# tvbgone.net
KiCad netlist of a schematic drawn in EAGLE
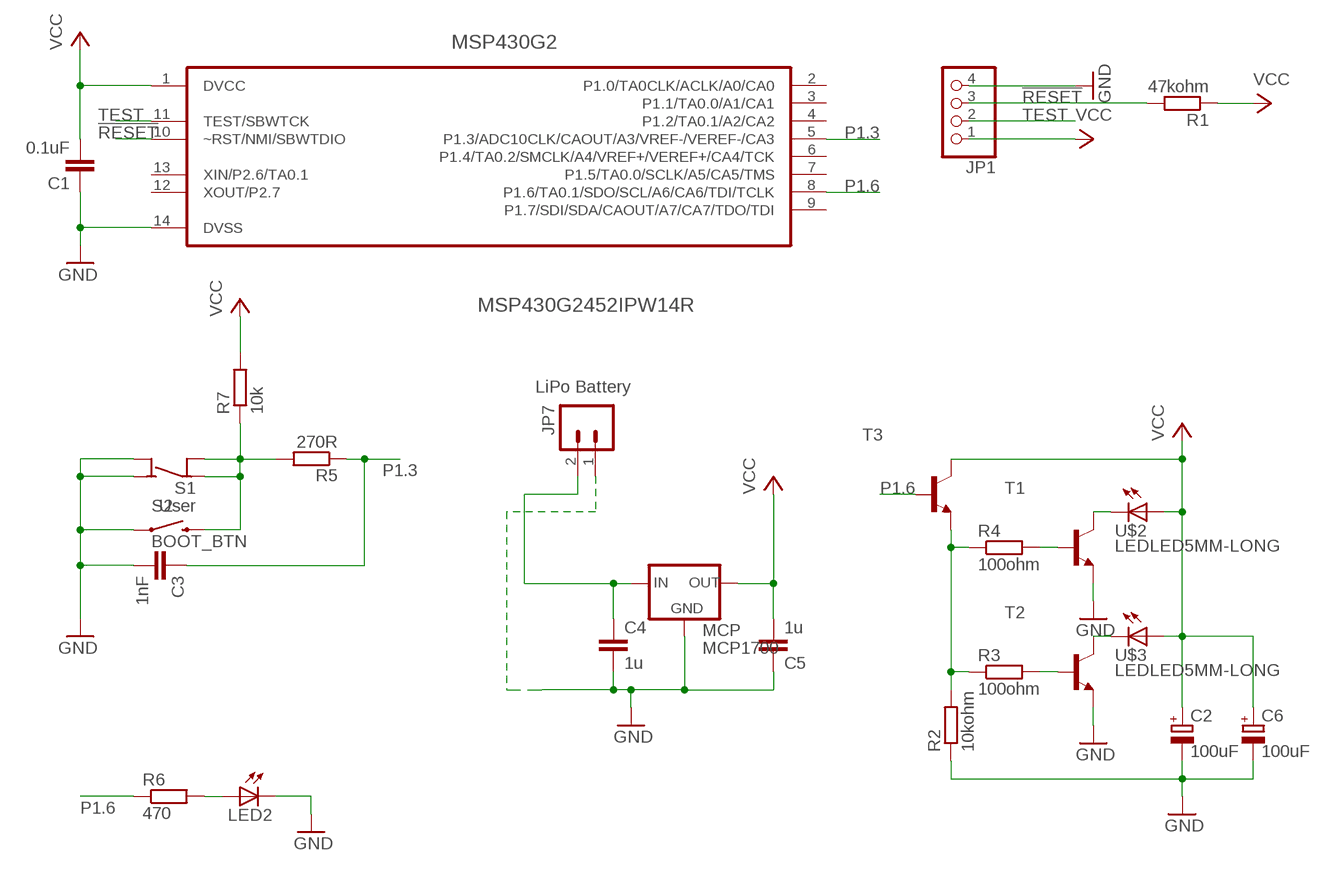
[diagram p0: schematic, sheet 1]

(export (version "E")
  (design (tool "Eeschema 10.0.6"))
  (components
    (comp (ref "C1")
      (value "0.1uF")
      (footprint "eagle-import:C0805")
      (libsource (lib "eagle-import") (part "resistor_C-EUC0805"))
    )
    (comp (ref "C2")
      (value "100uF")
      (footprint "eagle-import:153CLV-0505")
      (libsource (lib "eagle-import") (part "CPOL-EU153CLV-0505"))
    )
    (comp (ref "C3")
      (value "1nF")
      (footprint "eagle-import:C0805")
      (libsource (lib "eagle-import") (part "resistor_C-EUC0805"))
    )
    (comp (ref "C4")
      (value "1u")
      (footprint "eagle-import:C0805")
      (libsource (lib "eagle-import") (part "C-EUC0805"))
    )
    (comp (ref "C5")
      (value "1u")
      (footprint "eagle-import:C0805")
      (libsource (lib "eagle-import") (part "C-EUC0805"))
    )
    (comp (ref "C6")
      (value "100uF")
      (footprint "eagle-import:E3,5-8")
      (libsource (lib "eagle-import") (part "CPOL-EUE3.5-8"))
    )
    (comp (ref "JP1")
      (value "PINHD-1X4")
      (footprint "eagle-import:1X04")
      (libsource (lib "eagle-import") (part "PINHD-1X4"))
    )
    (comp (ref "JP7")
      (value "LiPo Battery")
      (footprint "eagle-import:JST-2-PTH")
      (libsource (lib "eagle-import") (part "M02JST-PTH-2"))
    )
    (comp (ref "LED2")
      (value "0")
      (footprint "eagle-import:CHIPLED_1206")
      (libsource (lib "eagle-import") (part "LEDCHIPLED_1206"))
    )
    (comp (ref "MCP")
      (value "MCP1700")
      (footprint "eagle-import:SOT-23")
      (libsource (lib "eagle-import") (part "MCP1700SOT-23"))
    )
    (comp (ref "MSP430G2")
      (value "MSP430G2452IPW14R")
      (footprint "eagle-import:SOP65P640X120-14N")
      (libsource (lib "eagle-import") (part "MSP430G2452IPW14R"))
    )
    (comp (ref "R1")
      (value "47kohm")
      (footprint "eagle-import:R0805")
      (libsource (lib "eagle-import") (part "R-EU_R0805"))
    )
    (comp (ref "R2")
      (value "10kohm")
      (footprint "eagle-import:R0805")
      (libsource (lib "eagle-import") (part "R-EU_R0805"))
    )
    (comp (ref "R3")
      (value "100ohm")
      (footprint "eagle-import:R0805")
      (libsource (lib "eagle-import") (part "R-EU_R0805"))
    )
    (comp (ref "R4")
      (value "100ohm")
      (footprint "eagle-import:R0805")
      (libsource (lib "eagle-import") (part "R-EU_R0805"))
    )
    (comp (ref "R5")
      (value "270R")
      (footprint "eagle-import:R0805")
      (libsource (lib "eagle-import") (part "R-EU_R0805"))
    )
    (comp (ref "R6")
      (value "470")
      (footprint "eagle-import:R0805")
      (libsource (lib "eagle-import") (part "R-EU_R0805"))
    )
    (comp (ref "R7")
      (value "10k")
      (footprint "eagle-import:R0805")
      (libsource (lib "eagle-import") (part "R-EU_R0805"))
    )
    (comp (ref "S1")
      (value "User")
      (footprint "eagle-import:6MMTACTILE_4PIN")
      (libsource (lib "eagle-import") (part "SPST4"))
    )
    (comp (ref "S2")
      (value "BOOT_BTN")
      (footprint "eagle-import:TACTILE-SWITCH-1101NE")
      (libsource (lib "eagle-import") (part "SWITCH-MOMENTARY-2-SMD-1101NE"))
    )
    (comp (ref "T1")
      (value "MMBT2222ALT1-NPN-SOT23-BEC")
      (footprint "eagle-import:SOT23-BEC")
      (libsource (lib "eagle-import") (part "-NPN-SOT23-BECMMBT2222ALT1"))
    )
    (comp (ref "T2")
      (value "MMBT2222ALT1-NPN-SOT23-BEC")
      (footprint "eagle-import:SOT23-BEC")
      (libsource (lib "eagle-import") (part "-NPN-SOT23-BECMMBT2222ALT1"))
    )
    (comp (ref "T3")
      (value "MMBT2222ALT1-NPN-SOT23-BEC")
      (footprint "eagle-import:SOT23-BEC")
      (libsource (lib "eagle-import") (part "-NPN-SOT23-BECMMBT2222ALT1"))
    )
    (comp (ref "U$2")
      (value "LEDLED5MM-LONG")
      (footprint "eagle-import:LED5MM-LONG")
      (libsource (lib "eagle-import") (part "LEDLED5MM-LONG"))
    )
    (comp (ref "U$3")
      (value "LEDLED5MM-LONG")
      (footprint "eagle-import:LED5MM-LONG")
      (libsource (lib "eagle-import") (part "LEDLED5MM-LONG"))
    )
  )
  (nets
    (net (code "1") (name "/P1.3") (class "Default")
      (node (ref "C3") (pin "1") (pinfunction "1_1") (pintype "passive"))
      (node (ref "MSP430G2") (pin "5") (pinfunction "P1.3/ADC10CLK/CAOUT/A3/VREF-/VEREF-/CA3_5") (pintype "bidirectional"))
      (node (ref "R5") (pin "1") (pinfunction "1_1") (pintype "passive"))
    )
    (net (code "2") (name "/P1.6") (class "Default")
      (node (ref "MSP430G2") (pin "8") (pinfunction "P1.6/TA0.1/SDO/SCL/A6/CA6/TDI/TCLK_8") (pintype "bidirectional"))
      (node (ref "R6") (pin "1") (pinfunction "1_1") (pintype "passive"))
      (node (ref "T3") (pin "B") (pinfunction "B_B") (pintype "passive"))
    )
    (net (code "3") (name "/TEST") (class "Default")
      (node (ref "JP1") (pin "2") (pinfunction "2_2") (pintype "passive"))
      (node (ref "MSP430G2") (pin "11") (pinfunction "TEST/SBWTCK_11") (pintype "input"))
    )
    (net (code "4") (name "/~{RESET}") (class "Default")
      (node (ref "JP1") (pin "3") (pinfunction "3_3") (pintype "passive"))
      (node (ref "MSP430G2") (pin "10") (pinfunction "~{RST/NMI/SBWTDIO}_10") (pintype "input"))
      (node (ref "R1") (pin "2") (pinfunction "2_2") (pintype "passive"))
    )
    (net (code "5") (name "GND") (class "Default")
      (node (ref "C1") (pin "1") (pinfunction "1_1") (pintype "passive"))
      (node (ref "C2") (pin "-") (pinfunction "-_-") (pintype "passive"))
      (node (ref "C3") (pin "2") (pinfunction "2_2") (pintype "passive"))
      (node (ref "C4") (pin "2") (pinfunction "2_2") (pintype "passive"))
      (node (ref "C5") (pin "1") (pinfunction "1_1") (pintype "passive"))
      (node (ref "C6") (pin "-") (pinfunction "-_-") (pintype "passive"))
      (node (ref "JP1") (pin "4") (pinfunction "4_4") (pintype "passive"))
      (node (ref "JP7") (pin "1") (pinfunction "1_1") (pintype "passive"))
      (node (ref "LED2") (pin "C") (pinfunction "C_C") (pintype "passive"))
      (node (ref "MCP") (pin "1") (pinfunction "GND_1") (pintype "input"))
      (node (ref "MSP430G2") (pin "14") (pinfunction "DVSS_14") (pintype "power_in"))
      (node (ref "R2") (pin "1") (pinfunction "1_1") (pintype "passive"))
      (node (ref "S1") (pin "A1") (pinfunction "NO_A1") (pintype "passive"))
      (node (ref "S1") (pin "A2") (pinfunction "NO_A2") (pintype "passive"))
      (node (ref "S2") (pin "1") (pinfunction "1_1") (pintype "passive"))
      (node (ref "T1") (pin "E") (pinfunction "E_E") (pintype "passive"))
      (node (ref "T2") (pin "E") (pinfunction "E_E") (pintype "passive"))
    )
    (net (code "6") (name "Net-(LED2-PadA)") (class "Default")
      (node (ref "LED2") (pin "A") (pinfunction "A_A") (pintype "passive"))
      (node (ref "R6") (pin "2") (pinfunction "2_2") (pintype "passive"))
    )
    (net (code "7") (name "Net-(MCP-IN)") (class "Default")
      (node (ref "C4") (pin "1") (pinfunction "1_1") (pintype "passive"))
      (node (ref "JP7") (pin "2") (pinfunction "2_2") (pintype "passive"))
      (node (ref "MCP") (pin "3") (pinfunction "IN_3") (pintype "input"))
    )
    (net (code "8") (name "Net-(R2-Pad2)") (class "Default")
      (node (ref "R2") (pin "2") (pinfunction "2_2") (pintype "passive"))
      (node (ref "R3") (pin "1") (pinfunction "1_1") (pintype "passive"))
      (node (ref "R4") (pin "1") (pinfunction "1_1") (pintype "passive"))
      (node (ref "T3") (pin "E") (pinfunction "E_E") (pintype "passive"))
    )
    (net (code "9") (name "Net-(R3-Pad2)") (class "Default")
      (node (ref "R3") (pin "2") (pinfunction "2_2") (pintype "passive"))
      (node (ref "T2") (pin "B") (pinfunction "B_B") (pintype "passive"))
    )
    (net (code "10") (name "Net-(R4-Pad2)") (class "Default")
      (node (ref "R4") (pin "2") (pinfunction "2_2") (pintype "passive"))
      (node (ref "T1") (pin "B") (pinfunction "B_B") (pintype "passive"))
    )
    (net (code "11") (name "Net-(R5-Pad2)") (class "Default")
      (node (ref "R5") (pin "2") (pinfunction "2_2") (pintype "passive"))
      (node (ref "R7") (pin "1") (pinfunction "1_1") (pintype "passive"))
      (node (ref "S1") (pin "B1") (pinfunction "COM_B1") (pintype "passive"))
      (node (ref "S1") (pin "B2") (pinfunction "COM_B2") (pintype "passive"))
      (node (ref "S2") (pin "2") (pinfunction "2_2") (pintype "passive"))
    )
    (net (code "12") (name "Net-(T1-PadC)") (class "Default")
      (node (ref "T1") (pin "C") (pinfunction "C_C") (pintype "passive"))
      (node (ref "U$2") (pin "C") (pinfunction "C_C") (pintype "passive"))
    )
    (net (code "13") (name "Net-(T2-PadC)") (class "Default")
      (node (ref "T2") (pin "C") (pinfunction "C_C") (pintype "passive"))
      (node (ref "U$3") (pin "C") (pinfunction "C_C") (pintype "passive"))
    )
    (net (code "14") (name "VCC") (class "Default")
      (node (ref "C1") (pin "2") (pinfunction "2_2") (pintype "passive"))
      (node (ref "C2") (pin "+") (pinfunction "+_+") (pintype "passive"))
      (node (ref "C5") (pin "2") (pinfunction "2_2") (pintype "passive"))
      (node (ref "C6") (pin "+") (pinfunction "+_+") (pintype "passive"))
      (node (ref "JP1") (pin "1") (pinfunction "1_1") (pintype "passive"))
      (node (ref "MCP") (pin "2") (pinfunction "OUT_2") (pintype "passive"))
      (node (ref "MSP430G2") (pin "1") (pinfunction "DVCC_1") (pintype "power_in"))
      (node (ref "R1") (pin "1") (pinfunction "1_1") (pintype "passive"))
      (node (ref "R7") (pin "2") (pinfunction "2_2") (pintype "passive"))
      (node (ref "T3") (pin "C") (pinfunction "C_C") (pintype "passive"))
      (node (ref "U$2") (pin "A") (pinfunction "A_A") (pintype "passive"))
      (node (ref "U$3") (pin "A") (pinfunction "A_A") (pintype "passive"))
    )
    (net (code "15") (name "unconnected-(MSP430G2-P1.0{slash}TA0CLK{slash}ACLK{slash}A0{slash}CA0-Pad2)") (class "Default")
      (node (ref "MSP430G2") (pin "2") (pinfunction "P1.0/TA0CLK/ACLK/A0/CA0_2") (pintype "bidirectional"))
    )
    (net (code "16") (name "unconnected-(MSP430G2-P1.1{slash}TA0.0{slash}A1{slash}CA1-Pad3)") (class "Default")
      (node (ref "MSP430G2") (pin "3") (pinfunction "P1.1/TA0.0/A1/CA1_3") (pintype "bidirectional"))
    )
    (net (code "17") (name "unconnected-(MSP430G2-P1.2{slash}TA0.1{slash}A2{slash}CA2-Pad4)") (class "Default")
      (node (ref "MSP430G2") (pin "4") (pinfunction "P1.2/TA0.1/A2/CA2_4") (pintype "bidirectional"))
    )
    (net (code "18") (name "unconnected-(MSP430G2-P1.4{slash}TA0.2{slash}SMCLK{slash}A4{slash}VREF+{slash}VEREF+{slash}CA4{slash}TCK-Pad6)") (class "Default")
      (node (ref "MSP430G2") (pin "6") (pinfunction "P1.4/TA0.2/SMCLK/A4/VREF+/VEREF+/CA4/TCK_6") (pintype "bidirectional"))
    )
    (net (code "19") (name "unconnected-(MSP430G2-P1.5{slash}TA0.0{slash}SCLK{slash}A5{slash}CA5{slash}TMS-Pad7)") (class "Default")
      (node (ref "MSP430G2") (pin "7") (pinfunction "P1.5/TA0.0/SCLK/A5/CA5/TMS_7") (pintype "bidirectional"))
    )
    (net (code "20") (name "unconnected-(MSP430G2-P1.7{slash}SDI{slash}SDA{slash}CAOUT{slash}A7{slash}CA7{slash}TDO{slash}TDI-Pad9)") (class "Default")
      (node (ref "MSP430G2") (pin "9") (pinfunction "P1.7/SDI/SDA/CAOUT/A7/CA7/TDO/TDI_9") (pintype "bidirectional"))
    )
    (net (code "21") (name "unconnected-(MSP430G2-XIN{slash}P2.6{slash}TA0.1-Pad13)") (class "Default")
      (node (ref "MSP430G2") (pin "13") (pinfunction "XIN/P2.6/TA0.1_13") (pintype "bidirectional"))
    )
    (net (code "22") (name "unconnected-(MSP430G2-XOUT{slash}P2.7-Pad12)") (class "Default")
      (node (ref "MSP430G2") (pin "12") (pinfunction "XOUT/P2.7_12") (pintype "bidirectional"))
    )
  )
)
